# RGB.net
KiCad netlist of a schematic drawn in EasyEDA
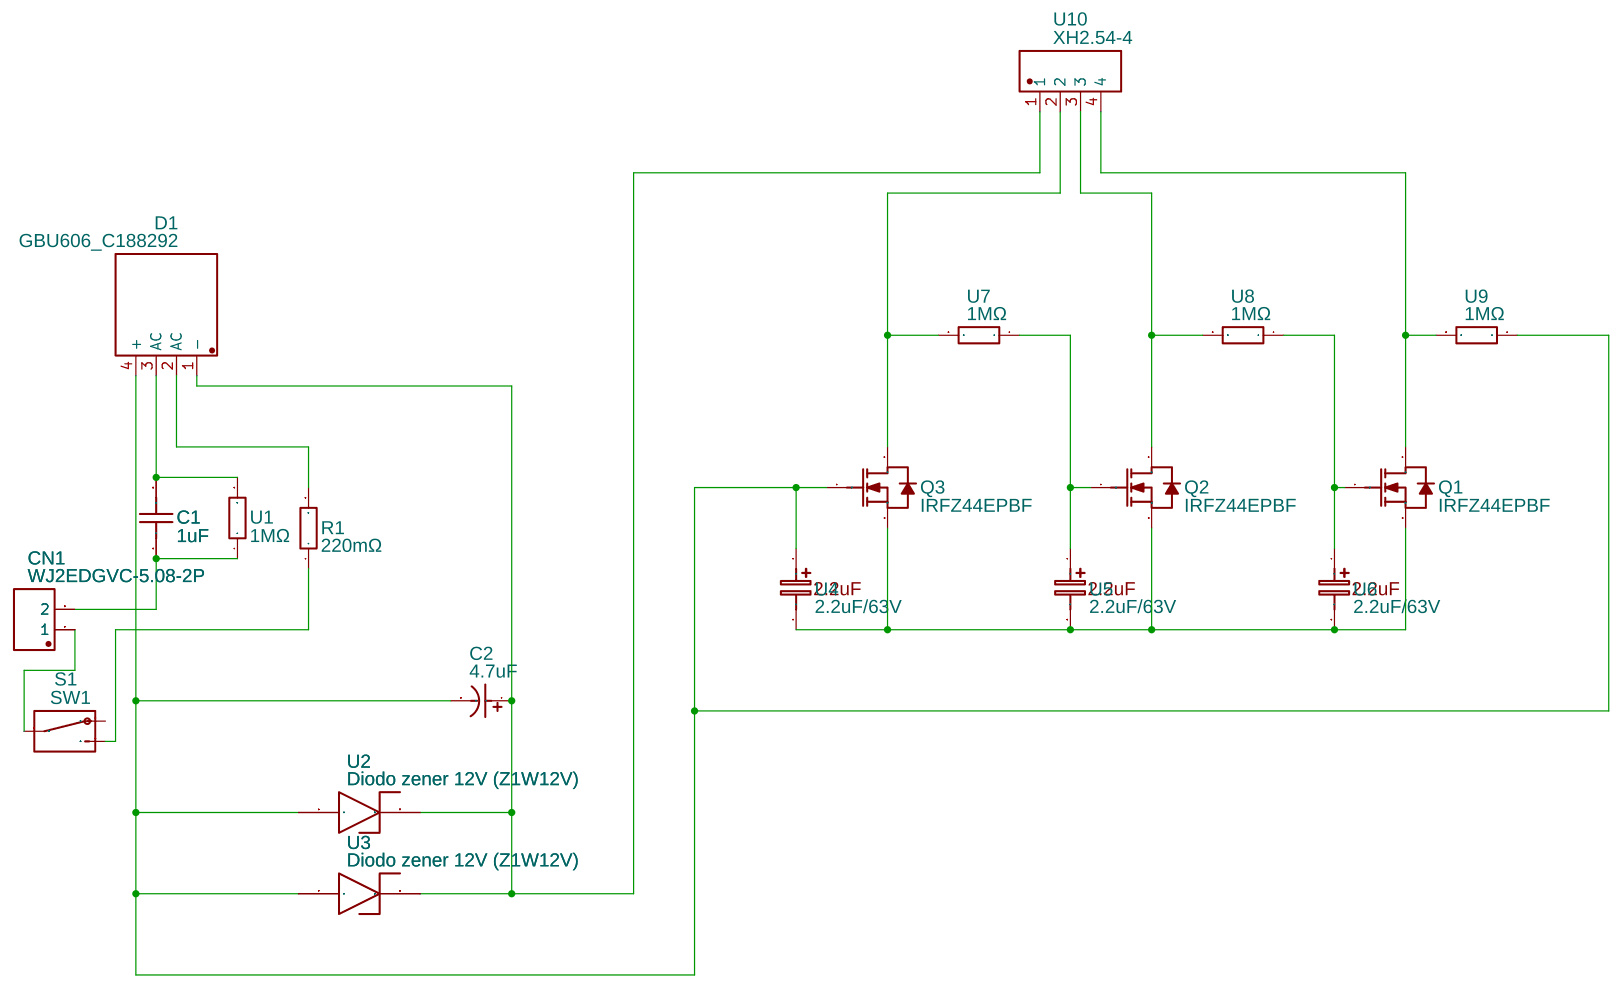
[diagram p0: schematic sheet]

(export (version "E")
  (design (tool "Eeschema 10.0.6"))
  (components
    (comp (ref "C1")
      (value "1uF")
      (fields (field (name "Manufacturer Part") "CBB22-105J-520V") (field (name "Manufacturer") "NDF(达孚)"))
      (libsource (lib "") (part "CBB22-105J-520V"))
    )
    (comp (ref "C2")
      (value "4.7uF")
      (fields
        (field (name "Manufacturer Part") "KM475M400G13RR0VH2FP0")
        (field (name "Manufacturer") "CX(承兴)")
      )
      (libsource (lib "") (part "4.7uF 400V"))
    )
    (comp (ref "CN1")
      (value "WJ2EDGVC-5.08-2P")
      (fields (field (name "Manufacturer") "KANGNEX(康奈克斯电气)"))
      (libsource (lib "") (part "WJ2EDGVC-5.08-2P"))
    )
    (comp (ref "D1")
      (value "GBU606_C188292")
      (fields (field (name "Manufacturer Part") "GBU606") (field (name "Manufacturer") "FMS(美丽微)"))
      (libsource (lib "") (part "GBU606_C188292"))
    )
    (comp (ref "Q1")
      (value "IRFZ44EPBF")
      (fields (field (name "Manufacturer") "Infineon(英飞凌)"))
      (libsource (lib "") (part "IRFZ44EPBF"))
    )
    (comp (ref "Q2")
      (value "IRFZ44EPBF")
      (fields (field (name "Manufacturer") "Infineon(英飞凌)"))
      (libsource (lib "") (part "IRFZ44EPBF"))
    )
    (comp (ref "Q3")
      (value "IRFZ44EPBF")
      (fields (field (name "Manufacturer") "Infineon(英飞凌)"))
      (libsource (lib "") (part "IRFZ44EPBF"))
    )
    (comp (ref "R1")
      (value "220mΩ")
      (fields (field (name "Manufacturer Part") "CR-L5W0.22Ω 5% P") (field (name "Manufacturer") "CCO(千志电子)"))
      (libsource (lib "") (part "CR-L5W0.22ΩJ"))
    )
    (comp (ref "S1") (value "SW1") (libsource (lib "") (part "SW1")))
    (comp (ref "U1")
      (value "1MΩ")
      (fields (field (name "Manufacturer Part") "FMP100FRE52-1M") (field (name "Manufacturer") "YAGEO(国巨)"))
      (libsource (lib "") (part "FMP100FRE52-1M_1"))
    )
    (comp (ref "U2")
      (value "Diodo zener 12V (Z1W12V)")
      (libsource (lib "") (part "Diodo zener 12V (Z1W12V)"))
    )
    (comp (ref "U3")
      (value "Diodo zener 12V (Z1W12V)")
      (libsource (lib "") (part "Diodo zener 12V (Z1W12V)"))
    )
    (comp (ref "U4") (value "2.2uF/63V") (libsource (lib "") (part "2.2uF/63V")))
    (comp (ref "U5") (value "2.2uF/63V") (libsource (lib "") (part "2.2uF/63V_1")))
    (comp (ref "U6") (value "2.2uF/63V") (libsource (lib "") (part "2.2uF/63V_1")))
    (comp (ref "U7")
      (value "1MΩ")
      (fields (field (name "Manufacturer Part") "FMP100FRE52-1M") (field (name "Manufacturer") "YAGEO(国巨)"))
      (libsource (lib "") (part "FMP100FRE52-1M"))
    )
    (comp (ref "U8")
      (value "1MΩ")
      (fields (field (name "Manufacturer Part") "FMP100FRE52-1M") (field (name "Manufacturer") "YAGEO(国巨)"))
      (libsource (lib "") (part "FMP100FRE52-1M"))
    )
    (comp (ref "U9")
      (value "1MΩ")
      (fields (field (name "Manufacturer Part") "FMP100FRE52-1M") (field (name "Manufacturer") "YAGEO(国巨)"))
      (libsource (lib "") (part "FMP100FRE52-1M"))
    )
    (comp (ref "U10") (value "XH2.54-4") (libsource (lib "") (part "XH2.54-4")))
  )
  (nets
    (net (code "1") (name "Net-(C1-Pad1)") (class "Default")
      (node (ref "C1") (pin "1") (pinfunction "1_1") (pintype "unspecified"))
      (node (ref "CN1") (pin "2") (pinfunction "2_2") (pintype "unspecified"))
      (node (ref "U1") (pin "1") (pinfunction "1_1") (pintype "unspecified"))
    )
    (net (code "2") (name "Net-(C1-Pad2)") (class "Default")
      (node (ref "C1") (pin "2") (pinfunction "2_2") (pintype "unspecified"))
      (node (ref "D1") (pin "3") (pinfunction "AC_3") (pintype "unspecified"))
      (node (ref "U1") (pin "2") (pinfunction "2_2") (pintype "unspecified"))
    )
    (net (code "3") (name "Net-(D1-+)") (class "Default")
      (node (ref "C2") (pin "2") (pinfunction "2_2") (pintype "input"))
      (node (ref "D1") (pin "4") (pinfunction "+_4") (pintype "unspecified"))
      (node (ref "Q3") (pin "1") (pinfunction "G_1") (pintype "unspecified"))
      (node (ref "U2") (pin "1") (pinfunction "1_1") (pintype "unspecified"))
      (node (ref "U3") (pin "1") (pinfunction "1_1") (pintype "unspecified"))
      (node (ref "U4") (pin "1") (pinfunction "1_1") (pintype "unspecified"))
      (node (ref "U9") (pin "1") (pinfunction "1_1") (pintype "unspecified"))
    )
    (net (code "4") (name "Net-(D1--)") (class "Default")
      (node (ref "C2") (pin "1") (pinfunction "1_1") (pintype "input"))
      (node (ref "D1") (pin "1") (pinfunction "-_1") (pintype "unspecified"))
      (node (ref "U10") (pin "1") (pinfunction "1_1") (pintype "unspecified"))
      (node (ref "U2") (pin "2") (pinfunction "2_2") (pintype "unspecified"))
      (node (ref "U3") (pin "2") (pinfunction "2_2") (pintype "unspecified"))
    )
    (net (code "5") (name "Net-(D1-AC-Pad2)") (class "Default")
      (node (ref "D1") (pin "2") (pinfunction "AC_2") (pintype "unspecified"))
      (node (ref "R1") (pin "2") (pinfunction "2_2") (pintype "unspecified"))
    )
    (net (code "6") (name "Net-(Q1-D)") (class "Default")
      (node (ref "Q1") (pin "2") (pinfunction "D_2") (pintype "unspecified"))
      (node (ref "U10") (pin "4") (pinfunction "4_4") (pintype "unspecified"))
      (node (ref "U9") (pin "2") (pinfunction "2_2") (pintype "unspecified"))
    )
    (net (code "7") (name "Net-(Q1-G)") (class "Default")
      (node (ref "Q1") (pin "1") (pinfunction "G_1") (pintype "unspecified"))
      (node (ref "U6") (pin "1") (pinfunction "1_1") (pintype "unspecified"))
      (node (ref "U8") (pin "1") (pinfunction "1_1") (pintype "unspecified"))
    )
    (net (code "8") (name "Net-(Q1-S)") (class "Default")
      (node (ref "Q1") (pin "3") (pinfunction "S_3") (pintype "unspecified"))
      (node (ref "Q2") (pin "3") (pinfunction "S_3") (pintype "unspecified"))
      (node (ref "Q3") (pin "3") (pinfunction "S_3") (pintype "unspecified"))
      (node (ref "U4") (pin "2") (pinfunction "2_2") (pintype "unspecified"))
      (node (ref "U5") (pin "2") (pinfunction "2_2") (pintype "unspecified"))
      (node (ref "U6") (pin "2") (pinfunction "2_2") (pintype "unspecified"))
    )
    (net (code "9") (name "Net-(Q2-D)") (class "Default")
      (node (ref "Q2") (pin "2") (pinfunction "D_2") (pintype "unspecified"))
      (node (ref "U10") (pin "3") (pinfunction "3_3") (pintype "unspecified"))
      (node (ref "U8") (pin "2") (pinfunction "2_2") (pintype "unspecified"))
    )
    (net (code "10") (name "Net-(Q2-G)") (class "Default")
      (node (ref "Q2") (pin "1") (pinfunction "G_1") (pintype "unspecified"))
      (node (ref "U5") (pin "1") (pinfunction "1_1") (pintype "unspecified"))
      (node (ref "U7") (pin "1") (pinfunction "1_1") (pintype "unspecified"))
    )
    (net (code "11") (name "Net-(Q3-D)") (class "Default")
      (node (ref "Q3") (pin "2") (pinfunction "D_2") (pintype "unspecified"))
      (node (ref "U10") (pin "2") (pinfunction "2_2") (pintype "unspecified"))
      (node (ref "U7") (pin "2") (pinfunction "2_2") (pintype "unspecified"))
    )
    (net (code "12") (name "Net-(S1-P)") (class "Default")
      (node (ref "CN1") (pin "1") (pinfunction "1_1") (pintype "unspecified"))
      (node (ref "S1") (pin "2") (pinfunction "P_2") (pintype "bidirectional"))
    )
    (net (code "13") (name "Net-(S1-S)") (class "Default")
      (node (ref "R1") (pin "1") (pinfunction "1_1") (pintype "unspecified"))
      (node (ref "S1") (pin "3") (pinfunction "S_3") (pintype "bidirectional"))
    )
    (net (code "14") (name "unconnected-(S1-O-Pad1)") (class "Default")
      (node (ref "S1") (pin "1") (pinfunction "O_1") (pintype "bidirectional"))
    )
  )
)
